# DB_LEDS.net
KiCad netlist of a schematic drawn in Altium Designer
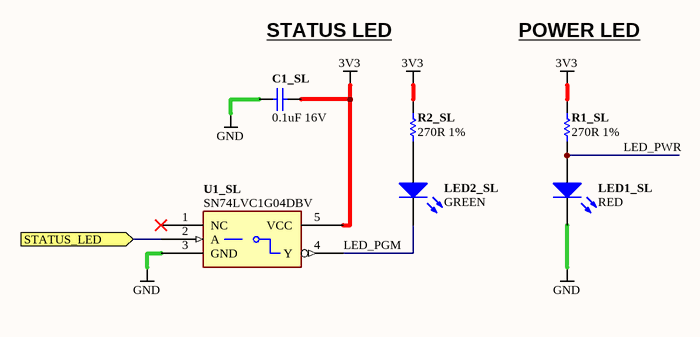
[diagram p0: DB_LEDS.SchDoc]

(export (version "E")
  (design (tool "Eeschema 10.0.6"))
  (components
    (comp (ref "C1_SL")
      (value "0.1uF 16V")
      (footprint "CAPC1005-STAR")
      (description "Capacitor, Ceramic, 0.1uF 10% 16V 0402 (1005) X7R")
      (fields (field (name "TOLERANCE") "10 %"))
      (libsource (lib "AltiumDesignLibrary") (part "CAP-NP"))
    )
    (comp (ref "LED1_SL")
      (value "RED")
      (footprint "LED2012-STAR")
      (description "LED, Red 0805 (2013) HSMH-C170")
      (libsource (lib "AltiumDesignLibrary") (part "DIO-LED-1S"))
    )
    (comp (ref "LED2_SL")
      (value "GREEN")
      (footprint "LED2012-STAR")
      (description "LED, Green 0805 (2012) KP-2012SGD")
      (libsource (lib "AltiumDesignLibrary") (part "DIO-LED-1S"))
    )
    (comp (ref "R1_SL")
      (value "270R 1%")
      (footprint "RESC1005-STAR")
      (description "Resistor, 270R 1% 0402 (1005)")
      (fields (field (name "TOLERANCE") "1 %"))
      (libsource (lib "AltiumDesignLibrary") (part "RES"))
    )
    (comp (ref "R2_SL")
      (value "270R 1%")
      (footprint "RESC1005-STAR")
      (description "Resistor, 270R 1% 0402 (1005)")
      (fields (field (name "TOLERANCE") "1 %"))
      (libsource (lib "AltiumDesignLibrary") (part "RES"))
    )
    (comp (ref "U1_SL")
      (value "SN74LVC1G04DBV")
      (footprint "SOT95P280-5")
      (description "SN74LVC1G04DBV, Single Inverter Gate, 1.65-V to 5.5-V")
      (libsource (lib "AltiumDesignLibrary") (part "SN74LVC1G04DBV"))
    )
  )
  (nets
    (net (code "1") (name "/LED_PGM") (class "Default")
      (node (ref "LED2_SL") (pin "2") (pinfunction "K_2") (pintype "passive"))
      (node (ref "U1_SL") (pin "4") (pinfunction "Y_4") (pintype "output"))
    )
    (net (code "2") (name "/LED_PWR") (class "Default")
      (node (ref "LED1_SL") (pin "1") (pinfunction "A_1") (pintype "passive"))
      (node (ref "R1_SL") (pin "2") (pinfunction "2_2") (pintype "passive"))
    )
    (net (code "3") (name "/STATUS_LED") (class "Default")
      (node (ref "U1_SL") (pin "2") (pinfunction "A_2") (pintype "input"))
    )
    (net (code "4") (name "3V3") (class "Default")
      (node (ref "C1_SL") (pin "2") (pinfunction "2_2") (pintype "passive"))
      (node (ref "R1_SL") (pin "1") (pinfunction "1_1") (pintype "passive"))
      (node (ref "R2_SL") (pin "1") (pinfunction "1_1") (pintype "passive"))
      (node (ref "U1_SL") (pin "5") (pinfunction "VCC_5") (pintype "power_in"))
    )
    (net (code "5") (name "GND") (class "Default")
      (node (ref "C1_SL") (pin "1") (pinfunction "1_1") (pintype "passive"))
      (node (ref "LED1_SL") (pin "2") (pinfunction "K_2") (pintype "passive"))
      (node (ref "U1_SL") (pin "3") (pinfunction "GND_3") (pintype "power_in"))
    )
    (net (code "6") (name "Net-(LED2_SL-A)") (class "Default")
      (node (ref "LED2_SL") (pin "1") (pinfunction "A_1") (pintype "passive"))
      (node (ref "R2_SL") (pin "2") (pinfunction "2_2") (pintype "passive"))
    )
    (net (code "7") (name "unconnected-(U1_SL-NC-Pad1)") (class "Default")
      (node (ref "U1_SL") (pin "1") (pinfunction "NC_1") (pintype "passive+no_connect"))
    )
  )
)
